# espPixel.net
KiCad netlist of a schematic drawn in EAGLE
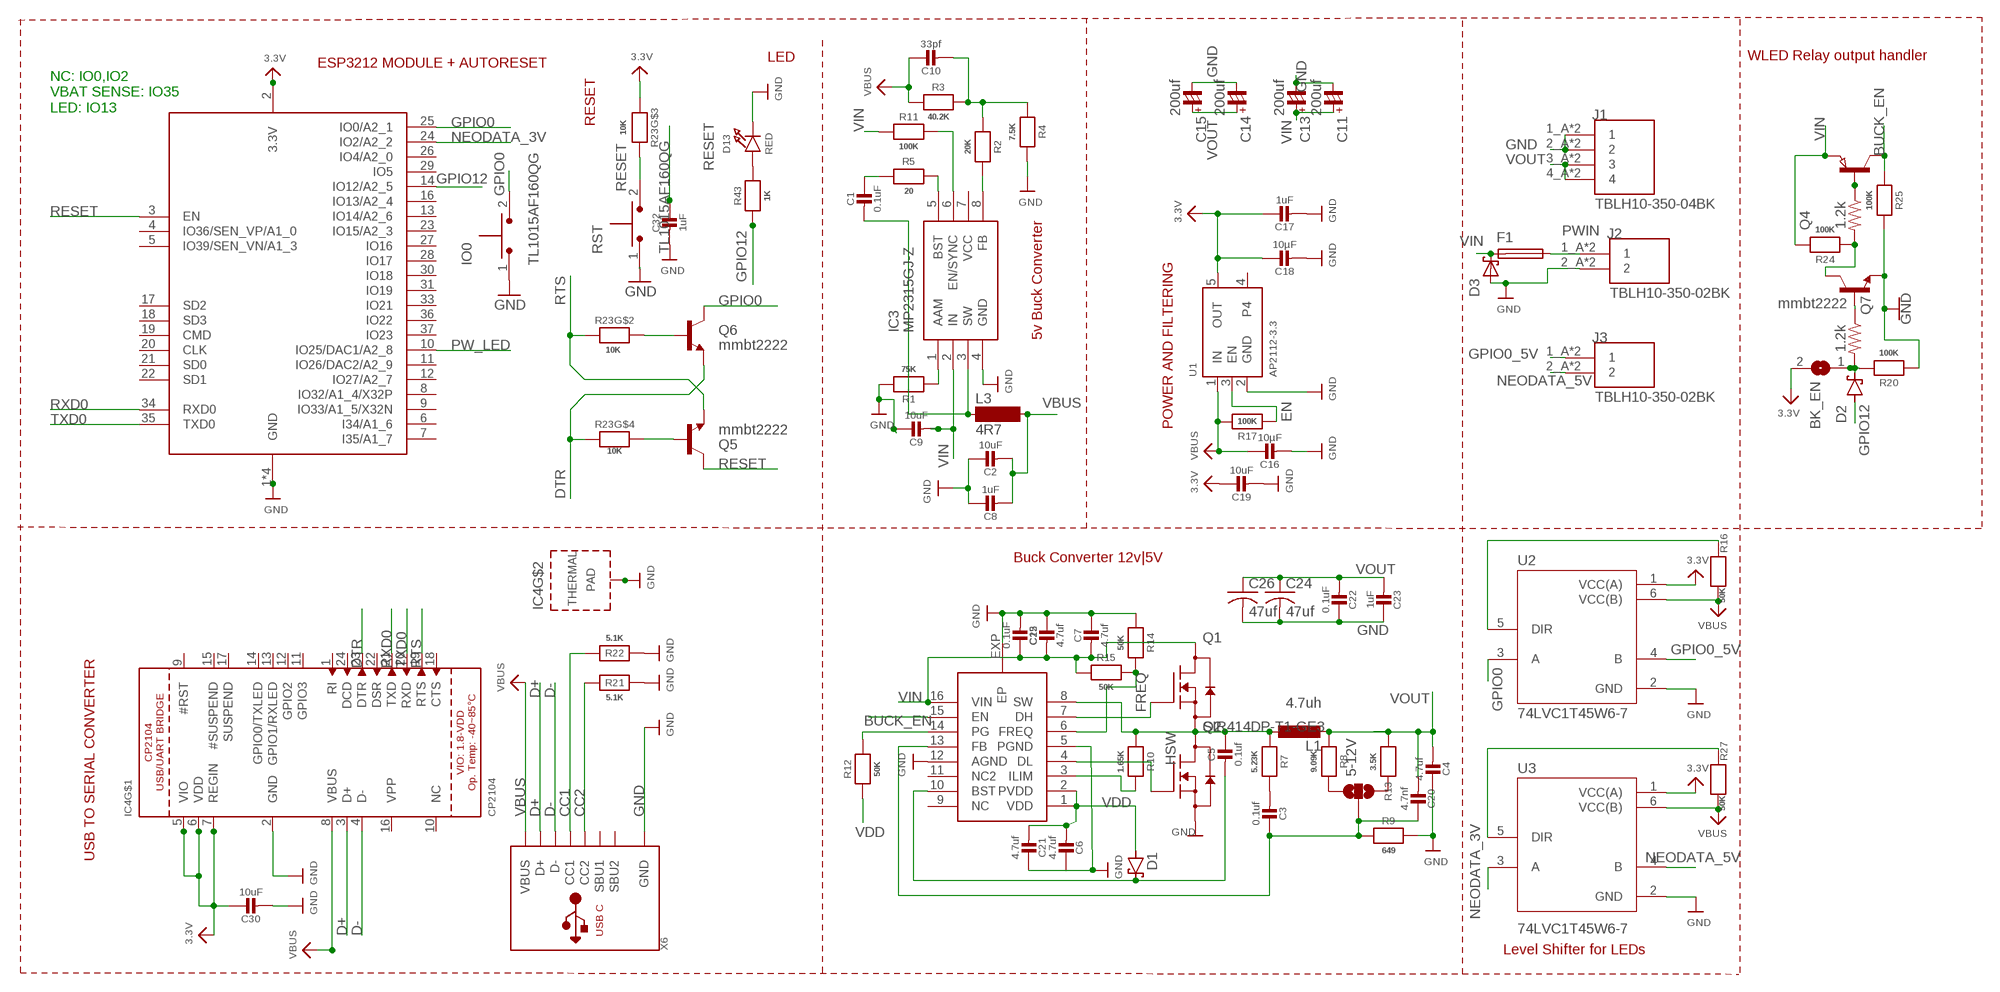
[diagram p0: schematic, sheet 1]

(export (version "E")
  (design (tool "Eeschema 10.0.6"))
  (components
    (comp (ref "5-12V")
      (value "JUMPER-SMT_3_NO_NO-SILK")
      (footprint "eagle-import:SMT-JUMPER_3_NO_NO-SILK")
      (libsource (lib "eagle-import") (part "JUMPER-SMT_3_NO_NO-SILK"))
    )
    (comp (ref "BK_EN")
      (value "SJ")
      (footprint "eagle-import:SJ")
      (libsource (lib "eagle-import") (part "SJ"))
    )
    (comp (ref "C1")
      (value "0.1uF")
      (footprint "eagle-import:0603-NO@1")
      (libsource (lib "eagle-import") (part "CAP_CERAMIC0603_NO"))
    )
    (comp (ref "C2")
      (value "10uF")
      (footprint "eagle-import:0603-NO@1")
      (libsource (lib "eagle-import") (part "CAP_CERAMIC0603_NO"))
    )
    (comp (ref "C3")
      (value "0.1uf")
      (footprint "eagle-import:0603-NO@1")
      (libsource (lib "eagle-import") (part "CAP_CERAMIC0603_NO"))
    )
    (comp (ref "C4")
      (value "4.7uf")
      (footprint "eagle-import:0805_10MGAP")
      (libsource (lib "eagle-import") (part "CAP_CERAMIC0805_10MGAP"))
    )
    (comp (ref "C5")
      (value "0.1uf")
      (footprint "eagle-import:0603-NO@1")
      (libsource (lib "eagle-import") (part "CAP_CERAMIC0603_NO"))
    )
    (comp (ref "C6")
      (value "4.7uf")
      (footprint "eagle-import:0603-NO@1")
      (libsource (lib "eagle-import") (part "CAP_CERAMIC0603_NO"))
    )
    (comp (ref "C7")
      (value "4.7uf")
      (footprint "eagle-import:0805_10MGAP")
      (libsource (lib "eagle-import") (part "CAP_CERAMIC0805_10MGAP"))
    )
    (comp (ref "C8")
      (value "1uF")
      (footprint "eagle-import:0603-NO@1")
      (libsource (lib "eagle-import") (part "CAP_CERAMIC0603_NO"))
    )
    (comp (ref "C9")
      (value "10uF")
      (footprint "eagle-import:0805_10MGAP")
      (libsource (lib "eagle-import") (part "CAP_CERAMIC0805_10MGAP"))
    )
    (comp (ref "C10")
      (value "33pf")
      (footprint "eagle-import:0603-NO@1")
      (libsource (lib "eagle-import") (part "CAP_CERAMIC0603_NO"))
    )
    (comp (ref "C11")
      (value "200uf")
      (footprint "eagle-import:CSV-E_F")
      (libsource (lib "eagle-import") (part "CP_SV-E/F"))
    )
    (comp (ref "C12")
      (value "4.7uf")
      (footprint "eagle-import:0805_10MGAP")
      (libsource (lib "eagle-import") (part "CAP_CERAMIC0805_10MGAP"))
    )
    (comp (ref "C13")
      (value "200uf")
      (footprint "eagle-import:CSV-E_F")
      (libsource (lib "eagle-import") (part "CP_SV-E/F"))
    )
    (comp (ref "C14")
      (value "200uf")
      (footprint "eagle-import:CSV-E_F")
      (libsource (lib "eagle-import") (part "CP_SV-E/F"))
    )
    (comp (ref "C15")
      (value "200uf")
      (footprint "eagle-import:CSV-E_F")
      (libsource (lib "eagle-import") (part "CP_SV-E/F"))
    )
    (comp (ref "C16")
      (value "10µF")
      (footprint "eagle-import:0805-NO")
      (libsource (lib "eagle-import") (part "CAP_CERAMIC0805-NOOUTLINE"))
    )
    (comp (ref "C17")
      (value "1uF")
      (footprint "eagle-import:0603-NO@1")
      (libsource (lib "eagle-import") (part "CAP_CERAMIC0603_NO"))
    )
    (comp (ref "C18")
      (value "10µF")
      (footprint "eagle-import:0805-NO")
      (libsource (lib "eagle-import") (part "CAP_CERAMIC0805-NOOUTLINE"))
    )
    (comp (ref "C19")
      (value "10uF")
      (footprint "eagle-import:0805-NO")
      (libsource (lib "eagle-import") (part "CAP_CERAMIC0805-NOOUTLINE"))
    )
    (comp (ref "C20")
      (value "4.7nf")
      (footprint "eagle-import:0603-NO@1")
      (libsource (lib "eagle-import") (part "CAP_CERAMIC0603_NO"))
    )
    (comp (ref "C21")
      (value "4.7uf")
      (footprint "eagle-import:0603-NO@1")
      (libsource (lib "eagle-import") (part "CAP_CERAMIC0603_NO"))
    )
    (comp (ref "C22")
      (value "0.1uF")
      (footprint "eagle-import:0603-NO@1")
      (libsource (lib "eagle-import") (part "CAP_CERAMIC0603_NO"))
    )
    (comp (ref "C23")
      (value "1uF")
      (footprint "eagle-import:0603-NO@1")
      (libsource (lib "eagle-import") (part "CAP_CERAMIC0603_NO"))
    )
    (comp (ref "C24")
      (value "47uf")
      (footprint "eagle-import:C3225")
      (libsource (lib "eagle-import") (part "C-USC3225"))
    )
    (comp (ref "C25")
      (value "0.1uF")
      (footprint "eagle-import:0603-NO@1")
      (libsource (lib "eagle-import") (part "CAP_CERAMIC0603_NO"))
    )
    (comp (ref "C26")
      (value "47uf")
      (footprint "eagle-import:C3225")
      (libsource (lib "eagle-import") (part "C-USC3225"))
    )
    (comp (ref "C30")
      (value "10uF")
      (footprint "eagle-import:0805-NO")
      (libsource (lib "eagle-import") (part "CAP_CERAMIC0805-NOOUTLINE"))
    )
    (comp (ref "C32")
      (value "1uF")
      (footprint "eagle-import:0603-NO@1")
      (libsource (lib "eagle-import") (part "CAP_CERAMIC0603_NO"))
    )
    (comp (ref "D1")
      (value "BAT60J")
      (footprint "eagle-import:SOD323_ST")
      (libsource (lib "eagle-import") (part "BAT60J"))
    )
    (comp (ref "D2")
      (value "BAT60J")
      (footprint "eagle-import:SOD323_ST")
      (libsource (lib "eagle-import") (part "BAT60J"))
    )
    (comp (ref "D3")
      (value "SCHOTTKY-DIODESMC")
      (footprint "eagle-import:SMC")
      (libsource (lib "eagle-import") (part "SCHOTTKY-DIODESMC"))
    )
    (comp (ref "D13")
      (value "RED")
      (footprint "eagle-import:CHIPLED_0805_NOOUTLINE")
      (libsource (lib "eagle-import") (part "LED0805_NOOUTLINE"))
    )
    (comp (ref "F1")
      (value "SMD-MICRO-FUSE-BLOCK")
      (footprint "eagle-import:OMNIBLOK")
      (libsource (lib "eagle-import") (part "SMD-MICRO-FUSE-BLOCK"))
    )
    (comp (ref "IC3")
      (value "MP2315GJ-Z")
      (footprint "eagle-import:SOT65P280X100-8N")
      (fields (field (name "MOUSER_PART_NUMBER") "946-MP2315GJZ"))
      (libsource (lib "eagle-import") (part "MP2315GJ-Z"))
    )
    (comp (ref "IC4")
      (value "CP2104")
      (footprint "eagle-import:QFN24_4MM_SMSC")
      (libsource (lib "eagle-import") (part "CP2104"))
    )
    (comp (ref "IO0")
      (value "TL1015AF160QG")
      (footprint "eagle-import:SW_TL1015AF160QG")
      (fields (field (name "MF") "E-Switch"))
      (libsource (lib "eagle-import") (part "TL1015AF160QG"))
    )
    (comp (ref "J1")
      (value "TBLH10-350-04BK")
      (footprint "eagle-import:CUI_TBLH10-350-04BK")
      (fields (field (name "MF") "CUI Devices"))
      (libsource (lib "eagle-import") (part "TBLH10-350-04BK"))
    )
    (comp (ref "J2")
      (value "TBLH10-350-02BK")
      (footprint "eagle-import:CUI_TBLH10-350-02BK")
      (fields (field (name "MF") "CUI Devices"))
      (libsource (lib "eagle-import") (part "TBLH10-350-02BK"))
    )
    (comp (ref "J3")
      (value "TBLH10-350-02BK")
      (footprint "eagle-import:CUI_TBLH10-350-02BK")
      (fields (field (name "MF") "CUI Devices"))
      (libsource (lib "eagle-import") (part "TBLH10-350-02BK"))
    )
    (comp (ref "L1")
      (value "4.7uh")
      (footprint "eagle-import:CEP125")
      (libsource (lib "eagle-import") (part "L-EUCEP125"))
    )
    (comp (ref "L3")
      (value "4R7")
      (footprint "eagle-import:MS50")
      (libsource (lib "eagle-import") (part "MS50"))
    )
    (comp (ref "Q1")
      (value "SIR414DP-T1-GE3")
      (footprint "eagle-import:TRANS_SQJ461EP-T1-GE3")
      (fields (field (name "MF") "Vishay Siliconix"))
      (libsource (lib "eagle-import") (part "SIR414DP-T1-GE3"))
    )
    (comp (ref "Q2")
      (value "SIR414DP-T1-GE3")
      (footprint "eagle-import:TRANS_SQJ461EP-T1-GE3")
      (fields (field (name "MF") "Vishay Siliconix"))
      (libsource (lib "eagle-import") (part "SIR414DP-T1-GE3"))
    )
    (comp (ref "Q4")
      (value "PNP-TRANSISTOR_SOT23")
      (footprint "eagle-import:SOT23")
      (libsource (lib "eagle-import") (part "PNP-TRANSISTOR_SOT23"))
    )
    (comp (ref "Q5")
      (value "mmbt2222")
      (footprint "eagle-import:SOT23-3")
      (libsource (lib "eagle-import") (part "TRANSISTOR_NPNSOT23-3"))
    )
    (comp (ref "Q6")
      (value "mmbt2222")
      (footprint "eagle-import:SOT23-3")
      (libsource (lib "eagle-import") (part "TRANSISTOR_NPNSOT23-3"))
    )
    (comp (ref "Q7")
      (value "mmbt2222")
      (footprint "eagle-import:SOT23-3")
      (libsource (lib "eagle-import") (part "TRANSISTOR_NPNSOT23-3"))
    )
    (comp (ref "R1")
      (value "75K")
      (footprint "eagle-import:0603-NO")
      (libsource (lib "eagle-import") (part "RESISTOR_0603_NOOUT"))
    )
    (comp (ref "R2")
      (value "20K")
      (footprint "eagle-import:0603-NO")
      (libsource (lib "eagle-import") (part "RESISTOR_0603_NOOUT"))
    )
    (comp (ref "R3")
      (value "40.2K")
      (footprint "eagle-import:0603-NO")
      (libsource (lib "eagle-import") (part "RESISTOR_0603_NOOUT"))
    )
    (comp (ref "R4")
      (value "7.5K")
      (footprint "eagle-import:0603-NO")
      (libsource (lib "eagle-import") (part "RESISTOR_0603_NOOUT"))
    )
    (comp (ref "R5")
      (value "20")
      (footprint "eagle-import:0603-NO")
      (libsource (lib "eagle-import") (part "RESISTOR_0603_NOOUT"))
    )
    (comp (ref "R6")
      (value "1.2k")
      (footprint "eagle-import:0603")
      (libsource (lib "eagle-import") (part "RESISTOR0603"))
    )
    (comp (ref "R7")
      (value "5.23K")
      (footprint "eagle-import:0603-NO")
      (libsource (lib "eagle-import") (part "RESISTOR_0603_NOOUT"))
    )
    (comp (ref "R8")
      (value "9.09K")
      (footprint "eagle-import:0603-NO")
      (libsource (lib "eagle-import") (part "RESISTOR_0603_NOOUT"))
    )
    (comp (ref "R9")
      (value "649")
      (footprint "eagle-import:0603-NO")
      (libsource (lib "eagle-import") (part "RESISTOR_0603_NOOUT"))
    )
    (comp (ref "R10")
      (value "1.65K")
      (footprint "eagle-import:0603-NO")
      (libsource (lib "eagle-import") (part "RESISTOR_0603_NOOUT"))
    )
    (comp (ref "R11")
      (value "100K")
      (footprint "eagle-import:0603-NO")
      (libsource (lib "eagle-import") (part "RESISTOR_0603_NOOUT"))
    )
    (comp (ref "R12")
      (value "50K")
      (footprint "eagle-import:0603-NO")
      (libsource (lib "eagle-import") (part "RESISTOR_0603_NOOUT"))
    )
    (comp (ref "R13")
      (value "3.5K")
      (footprint "eagle-import:0603-NO")
      (libsource (lib "eagle-import") (part "RESISTOR_0603_NOOUT"))
    )
    (comp (ref "R14")
      (value "50K")
      (footprint "eagle-import:0603-NO")
      (libsource (lib "eagle-import") (part "RESISTOR_0603_NOOUT"))
    )
    (comp (ref "R15")
      (value "50K")
      (footprint "eagle-import:0603-NO")
      (libsource (lib "eagle-import") (part "RESISTOR_0603_NOOUT"))
    )
    (comp (ref "R16")
      (value "50K")
      (footprint "eagle-import:0603-NO")
      (libsource (lib "eagle-import") (part "RESISTOR_0603_NOOUT"))
    )
    (comp (ref "R17")
      (value "100K")
      (footprint "eagle-import:0603-NO")
      (libsource (lib "eagle-import") (part "RESISTOR_0603_NOOUT"))
    )
    (comp (ref "R19")
      (value "1.2k")
      (footprint "eagle-import:0603")
      (libsource (lib "eagle-import") (part "RESISTOR0603"))
    )
    (comp (ref "R20")
      (value "100K")
      (footprint "eagle-import:0603-NO")
      (libsource (lib "eagle-import") (part "RESISTOR_0603_NOOUT"))
    )
    (comp (ref "R21")
      (value "5.1K")
      (footprint "eagle-import:0603-NO")
      (libsource (lib "eagle-import") (part "RESISTOR_0603_NOOUT"))
    )
    (comp (ref "R22")
      (value "5.1K")
      (footprint "eagle-import:0603-NO")
      (libsource (lib "eagle-import") (part "RESISTOR_0603_NOOUT"))
    )
    (comp (ref "R23")
      (value "10K")
      (footprint "eagle-import:RESPACK_4X0603")
      (libsource (lib "eagle-import") (part "RESISTOR_4PACK"))
    )
    (comp (ref "R24")
      (value "100K")
      (footprint "eagle-import:0603-NO")
      (libsource (lib "eagle-import") (part "RESISTOR_0603_NOOUT"))
    )
    (comp (ref "R25")
      (value "100K")
      (footprint "eagle-import:0603-NO")
      (libsource (lib "eagle-import") (part "RESISTOR_0603_NOOUT"))
    )
    (comp (ref "R27")
      (value "50K")
      (footprint "eagle-import:0603-NO")
      (libsource (lib "eagle-import") (part "RESISTOR_0603_NOOUT"))
    )
    (comp (ref "R43")
      (value "1K")
      (footprint "eagle-import:0603-NO")
      (libsource (lib "eagle-import") (part "RESISTOR_0603_NOOUT"))
    )
    (comp (ref "RST")
      (value "TL1015AF160QG")
      (footprint "eagle-import:SW_TL1015AF160QG")
      (fields (field (name "MF") "E-Switch"))
      (libsource (lib "eagle-import") (part "TL1015AF160QG"))
    )
    (comp (ref "U$1")
      (value "MIC2101QFN16")
      (footprint "eagle-import:QFN16")
      (libsource (lib "eagle-import") (part "MIC2101QFN16"))
    )
    (comp (ref "U1")
      (value "AP2112-3.3")
      (footprint "eagle-import:SOT23-5")
      (libsource (lib "eagle-import") (part "VREG_SOT23-5"))
    )
    (comp (ref "U2")
      (value "74LVC1T45W6-7")
      (footprint "eagle-import:SOT95P285X140-6N")
      (fields (field (name "MF") "Diodes Inc."))
      (libsource (lib "eagle-import") (part "74LVC1T45W6-7"))
    )
    (comp (ref "U3")
      (value "74LVC1T45W6-7")
      (footprint "eagle-import:SOT95P285X140-6N")
      (fields (field (name "MF") "Diodes Inc."))
      (libsource (lib "eagle-import") (part "74LVC1T45W6-7"))
    )
    (comp (ref "X6")
      (value "USB_C")
      (footprint "eagle-import:USB_C_CUSB31-CFM2AX-01-X")
      (libsource (lib "eagle-import") (part "USB_C"))
    )
    (comp (ref "X8")
      (value "ESP32_WROOM32_SKINNY")
      (footprint "eagle-import:WROOM32_SKINNY")
      (libsource (lib "eagle-import") (part "ESP32_WROOM32_SKINNY"))
    )
  )
  (nets
    (net (code "1") (name "/BUCK_EN") (class "Default")
      (node (ref "Q4") (pin "3") (pinfunction "C_3") (pintype "passive"))
      (node (ref "R25") (pin "1") (pinfunction "1_1") (pintype "passive"))
      (node (ref "U$1") (pin "15") (pinfunction "EN_15") (pintype "bidirectional"))
    )
    (net (code "2") (name "/CC1") (class "Default")
      (node (ref "R22") (pin "2") (pinfunction "2_2") (pintype "passive"))
      (node (ref "X6") (pin "A5") (pinfunction "CC1_A5") (pintype "bidirectional"))
    )
    (net (code "3") (name "/CC2") (class "Default")
      (node (ref "R21") (pin "2") (pinfunction "2_2") (pintype "passive"))
      (node (ref "X6") (pin "B5") (pinfunction "CC2_B5") (pintype "bidirectional"))
    )
    (net (code "4") (name "/D+") (class "Default")
      (node (ref "IC4") (pin "3") (pinfunction "D+_3") (pintype "bidirectional"))
      (node (ref "X6") (pin "A6") (pinfunction "D+_A6") (pintype "bidirectional"))
      (node (ref "X6") (pin "B6") (pinfunction "D+_B6") (pintype "bidirectional"))
    )
    (net (code "5") (name "/D-") (class "Default")
      (node (ref "IC4") (pin "4") (pinfunction "D-_4") (pintype "bidirectional"))
      (node (ref "X6") (pin "A7") (pinfunction "D-_A7") (pintype "bidirectional"))
      (node (ref "X6") (pin "B7") (pinfunction "D-_B7") (pintype "bidirectional"))
    )
    (net (code "6") (name "/DTR") (class "Default")
      (node (ref "IC4") (pin "23") (pinfunction "DTR_23") (pintype "output"))
      (node (ref "Q6") (pin "2") (pinfunction "E_2") (pintype "passive"))
      (node (ref "R23") (pin "4") (pinfunction "1_4") (pintype "passive"))
    )
    (net (code "7") (name "/EN") (class "Default")
      (node (ref "R17") (pin "1") (pinfunction "1_1") (pintype "passive"))
      (node (ref "U1") (pin "3") (pinfunction "EN_3") (pintype "input"))
    )
    (net (code "8") (name "/FREQ") (class "Default")
      (node (ref "R14") (pin "2") (pinfunction "2_2") (pintype "passive"))
      (node (ref "R15") (pin "2") (pinfunction "2_2") (pintype "passive"))
      (node (ref "U$1") (pin "6") (pinfunction "FREQ_6") (pintype "bidirectional"))
    )
    (net (code "9") (name "/GPIO0") (class "Default")
      (node (ref "IO0") (pin "2") (pinfunction "2_2") (pintype "passive"))
      (node (ref "Q6") (pin "3") (pinfunction "C_3") (pintype "passive"))
      (node (ref "U2") (pin "3") (pinfunction "A_3") (pintype "bidirectional"))
      (node (ref "X8") (pin "25") (pinfunction "IO0/A2_1_25") (pintype "bidirectional"))
    )
    (net (code "10") (name "/GPIO0_5V") (class "Default")
      (node (ref "J3") (pin "1_A") (pinfunction "1_1_A") (pintype "passive"))
      (node (ref "J3") (pin "1_B") (pinfunction "1_1_B") (pintype "passive"))
      (node (ref "U2") (pin "4") (pinfunction "B_4") (pintype "bidirectional"))
    )
    (net (code "11") (name "/GPIO12") (class "Default")
      (node (ref "D2") (pin "A") (pinfunction "A_A") (pintype "passive"))
      (node (ref "R43") (pin "1") (pinfunction "1_1") (pintype "passive"))
      (node (ref "X8") (pin "14") (pinfunction "IO12/A2_5_14") (pintype "bidirectional"))
    )
    (net (code "12") (name "/HSW") (class "Default")
      (node (ref "C5") (pin "1") (pinfunction "1_1") (pintype "passive"))
      (node (ref "L1") (pin "1") (pinfunction "1_1") (pintype "passive"))
      (node (ref "Q1") (pin "1") (pinfunction "S_1") (pintype "passive"))
      (node (ref "Q1") (pin "2") (pinfunction "S_2") (pintype "passive"))
      (node (ref "Q1") (pin "3") (pinfunction "S_3") (pintype "passive"))
      (node (ref "Q2") (pin "5") (pinfunction "D_5") (pintype "passive"))
      (node (ref "Q2") (pin "6") (pinfunction "D_6") (pintype "passive"))
      (node (ref "Q2") (pin "7") (pinfunction "D_7") (pintype "passive"))
      (node (ref "Q2") (pin "8") (pinfunction "D_8") (pintype "passive"))
      (node (ref "Q2") (pin "9") (pinfunction "D_9") (pintype "passive"))
      (node (ref "R10") (pin "1") (pinfunction "1_1") (pintype "passive"))
      (node (ref "R7") (pin "1") (pinfunction "1_1") (pintype "passive"))
      (node (ref "U$1") (pin "8") (pinfunction "SW_8") (pintype "bidirectional"))
    )
    (net (code "13") (name "/NEODATA_3V") (class "Default")
      (node (ref "U3") (pin "3") (pinfunction "A_3") (pintype "bidirectional"))
      (node (ref "X8") (pin "24") (pinfunction "IO2/A2_2_24") (pintype "bidirectional"))
    )
    (net (code "14") (name "/NEODATA_5V") (class "Default")
      (node (ref "J3") (pin "2_A") (pinfunction "2_2_A") (pintype "passive"))
      (node (ref "J3") (pin "2_B") (pinfunction "2_2_B") (pintype "passive"))
      (node (ref "U3") (pin "4") (pinfunction "B_4") (pintype "bidirectional"))
    )
    (net (code "15") (name "/PWIN") (class "Default")
      (node (ref "F1") (pin "P$1") (pinfunction "1_P$1") (pintype "passive"))
      (node (ref "J2") (pin "1_A") (pinfunction "1_1_A") (pintype "passive"))
      (node (ref "J2") (pin "1_B") (pinfunction "1_1_B") (pintype "passive"))
    )
    (net (code "16") (name "/PW_LED") (class "Default")
      (node (ref "X8") (pin "10") (pinfunction "IO25/DAC1/A2_8_10") (pintype "bidirectional"))
    )
    (net (code "17") (name "/RESET") (class "Default")
      (node (ref "C32") (pin "1") (pinfunction "1_1") (pintype "passive"))
      (node (ref "Q5") (pin "3") (pinfunction "C_3") (pintype "passive"))
      (node (ref "R23") (pin "6") (pinfunction "2_6") (pintype "passive"))
      (node (ref "RST") (pin "2") (pinfunction "2_2") (pintype "passive"))
      (node (ref "X8") (pin "3") (pinfunction "EN_3") (pintype "input"))
    )
    (net (code "18") (name "/RTS") (class "Default")
      (node (ref "IC4") (pin "19") (pinfunction "RTS_19") (pintype "output"))
      (node (ref "Q5") (pin "2") (pinfunction "E_2") (pintype "passive"))
      (node (ref "R23") (pin "2") (pinfunction "1_2") (pintype "passive"))
    )
    (net (code "19") (name "/RXD0") (class "Default")
      (node (ref "IC4") (pin "21") (pinfunction "TXD_21") (pintype "output"))
      (node (ref "X8") (pin "34") (pinfunction "RXD0_34") (pintype "input"))
    )
    (net (code "20") (name "/TXD0") (class "Default")
      (node (ref "IC4") (pin "20") (pinfunction "RXD_20") (pintype "input"))
      (node (ref "X8") (pin "35") (pinfunction "TXD0_35") (pintype "output"))
    )
    (net (code "21") (name "/VDD") (class "Default")
      (node (ref "C21") (pin "2") (pinfunction "2_2") (pintype "passive"))
      (node (ref "C6") (pin "2") (pinfunction "2_2") (pintype "passive"))
      (node (ref "D1") (pin "A") (pinfunction "A_A") (pintype "passive"))
      (node (ref "R12") (pin "1") (pinfunction "1_1") (pintype "passive"))
      (node (ref "U$1") (pin "1") (pinfunction "VDD_1") (pintype "power_in"))
      (node (ref "U$1") (pin "2") (pinfunction "PVDD_2") (pintype "bidirectional"))
    )
    (net (code "22") (name "/VIN") (class "Default")
      (node (ref "C11") (pin "+") (pinfunction "+_+") (pintype "passive"))
      (node (ref "C12") (pin "2") (pinfunction "2_2") (pintype "passive"))
      (node (ref "C13") (pin "+") (pinfunction "+_+") (pintype "passive"))
      (node (ref "C25") (pin "1") (pinfunction "1_1") (pintype "passive"))
      (node (ref "C7") (pin "2") (pinfunction "2_2") (pintype "passive"))
      (node (ref "C9") (pin "2") (pinfunction "2_2") (pintype "passive"))
      (node (ref "D3") (pin "C") (pinfunction "C_C") (pintype "passive"))
      (node (ref "F1") (pin "P$2") (pinfunction "2_P$2") (pintype "passive"))
      (node (ref "IC3") (pin "2") (pinfunction "IN_2") (pintype "input"))
      (node (ref "Q1") (pin "5") (pinfunction "D_5") (pintype "passive"))
      (node (ref "Q1") (pin "6") (pinfunction "D_6") (pintype "passive"))
      (node (ref "Q1") (pin "7") (pinfunction "D_7") (pintype "passive"))
      (node (ref "Q1") (pin "8") (pinfunction "D_8") (pintype "passive"))
      (node (ref "Q1") (pin "9") (pinfunction "D_9") (pintype "passive"))
      (node (ref "Q4") (pin "2") (pinfunction "E_2") (pintype "passive"))
      (node (ref "R11") (pin "1") (pinfunction "1_1") (pintype "passive"))
      (node (ref "R15") (pin "1") (pinfunction "1_1") (pintype "passive"))
      (node (ref "R24") (pin "2") (pinfunction "2_2") (pintype "passive"))
      (node (ref "U$1") (pin "16") (pinfunction "VIN_16") (pintype "input"))
    )
    (net (code "23") (name "/VOUT") (class "Default")
      (node (ref "C14") (pin "+") (pinfunction "+_+") (pintype "passive"))
      (node (ref "C15") (pin "+") (pinfunction "+_+") (pintype "passive"))
      (node (ref "C20") (pin "2") (pinfunction "2_2") (pintype "passive"))
      (node (ref "C22") (pin "2") (pinfunction "2_2") (pintype "passive"))
      (node (ref "C23") (pin "2") (pinfunction "2_2") (pintype "passive"))
      (node (ref "C24") (pin "1") (pinfunction "1_1") (pintype "passive"))
      (node (ref "C26") (pin "1") (pinfunction "1_1") (pintype "passive"))
      (node (ref "C4") (pin "2") (pinfunction "2_2") (pintype "passive"))
      (node (ref "J1") (pin "3_A") (pinfunction "3_3_A") (pintype "passive"))
      (node (ref "J1") (pin "3_B") (pinfunction "3_3_B") (pintype "passive"))
      (node (ref "J1") (pin "4_A") (pinfunction "4_4_A") (pintype "passive"))
      (node (ref "J1") (pin "4_B") (pinfunction "4_4_B") (pintype "passive"))
      (node (ref "L1") (pin "2") (pinfunction "2_2") (pintype "passive"))
      (node (ref "R13") (pin "1") (pinfunction "1_1") (pintype "passive"))
      (node (ref "R8") (pin "1") (pinfunction "1_1") (pintype "passive"))
    )
    (net (code "24") (name "3.3V") (class "Default")
      (node (ref "BK_EN") (pin "2") (pinfunction "2_2") (pintype "passive"))
      (node (ref "C17") (pin "1") (pinfunction "1_1") (pintype "passive"))
      (node (ref "C18") (pin "1") (pinfunction "1_1") (pintype "passive"))
      (node (ref "C19") (pin "1") (pinfunction "1_1") (pintype "passive"))
      (node (ref "C30") (pin "1") (pinfunction "1_1") (pintype "passive"))
      (node (ref "IC4") (pin "5") (pinfunction "VIO_5") (pintype "power_in"))
      (node (ref "IC4") (pin "6") (pinfunction "VDD_6") (pintype "power_in"))
      (node (ref "IC4") (pin "7") (pinfunction "REGIN_7") (pintype "power_in"))
      (node (ref "R23") (pin "3") (pinfunction "1_3") (pintype "passive"))
      (node (ref "U1") (pin "5") (pinfunction "OUT_5") (pintype "power_in"))
      (node (ref "U2") (pin "1") (pinfunction "VCC(A)_1") (pintype "power_in"))
      (node (ref "U3") (pin "1") (pinfunction "VCC(A)_1") (pintype "power_in"))
      (node (ref "X8") (pin "2") (pinfunction "3.3V_2") (pintype "passive"))
    )
    (net (code "25") (name "GND") (class "Default")
      (node (ref "C11") (pin "-") (pinfunction "-_-") (pintype "passive"))
      (node (ref "C12") (pin "1") (pinfunction "1_1") (pintype "passive"))
      (node (ref "C13") (pin "-") (pinfunction "-_-") (pintype "passive"))
      (node (ref "C14") (pin "-") (pinfunction "-_-") (pintype "passive"))
      (node (ref "C15") (pin "-") (pinfunction "-_-") (pintype "passive"))
      (node (ref "C16") (pin "2") (pinfunction "2_2") (pintype "passive"))
      (node (ref "C17") (pin "2") (pinfunction "2_2") (pintype "passive"))
      (node (ref "C18") (pin "2") (pinfunction "2_2") (pintype "passive"))
      (node (ref "C19") (pin "2") (pinfunction "2_2") (pintype "passive"))
      (node (ref "C2") (pin "1") (pinfunction "1_1") (pintype "passive"))
      (node (ref "C21") (pin "1") (pinfunction "1_1") (pintype "passive"))
      (node (ref "C22") (pin "1") (pinfunction "1_1") (pintype "passive"))
      (node (ref "C23") (pin "1") (pinfunction "1_1") (pintype "passive"))
      (node (ref "C24") (pin "2") (pinfunction "2_2") (pintype "passive"))
      (node (ref "C25") (pin "2") (pinfunction "2_2") (pintype "passive"))
      (node (ref "C26") (pin "2") (pinfunction "2_2") (pintype "passive"))
      (node (ref "C30") (pin "2") (pinfunction "2_2") (pintype "passive"))
      (node (ref "C32") (pin "2") (pinfunction "2_2") (pintype "passive"))
      (node (ref "C4") (pin "1") (pinfunction "1_1") (pintype "passive"))
      (node (ref "C6") (pin "1") (pinfunction "1_1") (pintype "passive"))
      (node (ref "C7") (pin "1") (pinfunction "1_1") (pintype "passive"))
      (node (ref "C8") (pin "1") (pinfunction "1_1") (pintype "passive"))
      (node (ref "C9") (pin "1") (pinfunction "1_1") (pintype "passive"))
      (node (ref "D13") (pin "C") (pinfunction "C_C") (pintype "passive"))
      (node (ref "D3") (pin "A") (pinfunction "A_A") (pintype "passive"))
      (node (ref "IC3") (pin "4") (pinfunction "GND_4") (pintype "power_in"))
      (node (ref "IC4") (pin "2") (pinfunction "GND_2") (pintype "power_in"))
      (node (ref "IC4") (pin "THERM") (pinfunction "TP_THERM") (pintype "power_in"))
      (node (ref "IO0") (pin "1") (pinfunction "1_1") (pintype "passive"))
      (node (ref "J1") (pin "1_A") (pinfunction "1_1_A") (pintype "passive"))
      (node (ref "J1") (pin "1_B") (pinfunction "1_1_B") (pintype "passive"))
      (node (ref "J1") (pin "2_A") (pinfunction "2_2_A") (pintype "passive"))
      (node (ref "J1") (pin "2_B") (pinfunction "2_2_B") (pintype "passive"))
      (node (ref "J2") (pin "2_A") (pinfunction "2_2_A") (pintype "passive"))
      (node (ref "J2") (pin "2_B") (pinfunction "2_2_B") (pintype "passive"))
      (node (ref "Q2") (pin "1") (pinfunction "S_1") (pintype "passive"))
      (node (ref "Q2") (pin "2") (pinfunction "S_2") (pintype "passive"))
      (node (ref "Q2") (pin "3") (pinfunction "S_3") (pintype "passive"))
      (node (ref "Q7") (pin "2") (pinfunction "E_2") (pintype "passive"))
      (node (ref "R1") (pin "2") (pinfunction "2_2") (pintype "passive"))
      (node (ref "R14") (pin "1") (pinfunction "1_1") (pintype "passive"))
      (node (ref "R20") (pin "1") (pinfunction "1_1") (pintype "passive"))
      (node (ref "R21") (pin "1") (pinfunction "1_1") (pintype "passive"))
      (node (ref "R22") (pin "1") (pinfunction "1_1") (pintype "passive"))
      (node (ref "R25") (pin "2") (pinfunction "2_2") (pintype "passive"))
      (node (ref "R4") (pin "2") (pinfunction "2_2") (pintype "passive"))
      (node (ref "R9") (pin "2") (pinfunction "2_2") (pintype "passive"))
      (node (ref "RST") (pin "1") (pinfunction "1_1") (pintype "passive"))
      (node (ref "U$1") (pin "12") (pinfunction "AGND_12") (pintype "bidirectional"))
      (node (ref "U$1") (pin "5") (pinfunction "PGND_5") (pintype "bidirectional"))
      (node (ref "U$1") (pin "EXP") (pinfunction "EP_EXP") (pintype "bidirectional"))
      (node (ref "U1") (pin "2") (pinfunction "GND_2") (pintype "power_in"))
      (node (ref "U2") (pin "2") (pinfunction "GND_2") (pintype "power_in"))
      (node (ref "U3") (pin "2") (pinfunction "GND_2") (pintype "power_in"))
      (node (ref "X6") (pin "A1B12") (pinfunction "GND_A1B12") (pintype "power_in"))
      (node (ref "X6") (pin "B1A12") (pinfunction "GND_B1A12") (pintype "power_in"))
      (node (ref "X8") (pin "1") (pinfunction "GND_1") (pintype "passive"))
      (node (ref "X8") (pin "15") (pinfunction "GND_15") (pintype "passive"))
      (node (ref "X8") (pin "38") (pinfunction "GND_38") (pintype "passive"))
      (node (ref "X8") (pin "P$1") (pinfunction "GND_P$1") (pintype "passive"))
    )
    (net (code "26") (name "Net-(5-12V-Pad1)") (class "Default")
      (node (ref "5-12V") (pin "1") (pinfunction "1_1") (pintype "passive"))
      (node (ref "R8") (pin "2") (pinfunction "2_2") (pintype "passive"))
    )
    (net (code "27") (name "Net-(5-12V-Pad3)") (class "Default")
      (node (ref "5-12V") (pin "3") (pinfunction "3_3") (pintype "passive"))
      (node (ref "R13") (pin "2") (pinfunction "2_2") (pintype "passive"))
    )
    (net (code "28") (name "Net-(BK_EN-Pad1)") (class "Default")
      (node (ref "BK_EN") (pin "1") (pinfunction "1_1") (pintype "passive"))
      (node (ref "D2") (pin "C") (pinfunction "C_C") (pintype "passive"))
      (node (ref "R20") (pin "2") (pinfunction "2_2") (pintype "passive"))
      (node (ref "R6") (pin "2") (pinfunction "2_2") (pintype "passive"))
    )
    (net (code "29") (name "Net-(C1-Pad1)") (class "Default")
      (node (ref "C1") (pin "1") (pinfunction "1_1") (pintype "passive"))
      (node (ref "R5") (pin "1") (pinfunction "1_1") (pintype "passive"))
    )
    (net (code "30") (name "Net-(C3-Pad2)") (class "Default")
      (node (ref "C3") (pin "2") (pinfunction "2_2") (pintype "passive"))
      (node (ref "R7") (pin "2") (pinfunction "2_2") (pintype "passive"))
    )
    (net (code "31") (name "Net-(C10-Pad2)") (class "Default")
      (node (ref "C10") (pin "2") (pinfunction "2_2") (pintype "passive"))
      (node (ref "R2") (pin "1") (pinfunction "1_1") (pintype "passive"))
      (node (ref "R3") (pin "2") (pinfunction "2_2") (pintype "passive"))
      (node (ref "R4") (pin "1") (pinfunction "1_1") (pintype "passive"))
    )
    (net (code "32") (name "Net-(D13-PadA)") (class "Default")
      (node (ref "D13") (pin "A") (pinfunction "A_A") (pintype "passive"))
      (node (ref "R43") (pin "2") (pinfunction "2_2") (pintype "passive"))
    )
    (net (code "33") (name "Net-(IC3-AAM)") (class "Default")
      (node (ref "IC3") (pin "1") (pinfunction "AAM_1") (pintype "bidirectional"))
      (node (ref "R1") (pin "1") (pinfunction "1_1") (pintype "passive"))
    )
    (net (code "34") (name "Net-(IC3-BST)") (class "Default")
      (node (ref "IC3") (pin "5") (pinfunction "BST_5") (pintype "bidirectional"))
      (node (ref "R5") (pin "2") (pinfunction "2_2") (pintype "passive"))
    )
    (net (code "35") (name "Net-(IC3-EN{slash}SYNC)") (class "Default")
      (node (ref "IC3") (pin "6") (pinfunction "EN/SYNC_6") (pintype "bidirectional"))
      (node (ref "R11") (pin "2") (pinfunction "2_2") (pintype "passive"))
    )
    (net (code "36") (name "Net-(IC3-FB)") (class "Default")
      (node (ref "IC3") (pin "8") (pinfunction "FB_8") (pintype "bidirectional"))
      (node (ref "R2") (pin "2") (pinfunction "2_2") (pintype "passive"))
    )
    (net (code "37") (name "Net-(IC3-SW)") (class "Default")
      (node (ref "C1") (pin "2") (pinfunction "2_2") (pintype "passive"))
      (node (ref "IC3") (pin "3") (pinfunction "SW_3") (pintype "bidirectional"))
      (node (ref "L3") (pin "1") (pinfunction "1_1") (pintype "passive"))
    )
    (net (code "38") (name "Net-(Q1-G)") (class "Default")
      (node (ref "Q1") (pin "4") (pinfunction "G_4") (pintype "passive"))
      (node (ref "U$1") (pin "7") (pinfunction "DH_7") (pintype "bidirectional"))
    )
    (net (code "39") (name "Net-(Q2-G)") (class "Default")
      (node (ref "Q2") (pin "4") (pinfunction "G_4") (pintype "passive"))
      (node (ref "U$1") (pin "4") (pinfunction "DL_4") (pintype "bidirectional"))
    )
    (net (code "40") (name "Net-(Q4-B)") (class "Default")
      (node (ref "Q4") (pin "1") (pinfunction "B_1") (pintype "passive"))
      (node (ref "R19") (pin "1") (pinfunction "1_1") (pintype "passive"))
    )
    (net (code "41") (name "Net-(Q5-B)") (class "Default")
      (node (ref "Q5") (pin "1") (pinfunction "B_1") (pintype "passive"))
      (node (ref "R23") (pin "5") (pinfunction "2_5") (pintype "passive"))
    )
    (net (code "42") (name "Net-(Q6-B)") (class "Default")
      (node (ref "Q6") (pin "1") (pinfunction "B_1") (pintype "passive"))
      (node (ref "R23") (pin "7") (pinfunction "2_7") (pintype "passive"))
    )
    (net (code "43") (name "Net-(Q7-B)") (class "Default")
      (node (ref "Q7") (pin "1") (pinfunction "B_1") (pintype "passive"))
      (node (ref "R6") (pin "1") (pinfunction "1_1") (pintype "passive"))
    )
    (net (code "44") (name "Net-(Q7-C)") (class "Default")
      (node (ref "Q7") (pin "3") (pinfunction "C_3") (pintype "passive"))
      (node (ref "R19") (pin "2") (pinfunction "2_2") (pintype "passive"))
      (node (ref "R24") (pin "1") (pinfunction "1_1") (pintype "passive"))
    )
    (net (code "45") (name "Net-(U$1-BST)") (class "Default")
      (node (ref "C5") (pin "2") (pinfunction "2_2") (pintype "passive"))
      (node (ref "D1") (pin "C") (pinfunction "C_C") (pintype "passive"))
      (node (ref "U$1") (pin "10") (pinfunction "BST_10") (pintype "bidirectional"))
    )
    (net (code "46") (name "Net-(U$1-FB)") (class "Default")
      (node (ref "5-12V") (pin "2") (pinfunction "2_2") (pintype "passive"))
      (node (ref "C20") (pin "1") (pinfunction "1_1") (pintype "passive"))
      (node (ref "C3") (pin "1") (pinfunction "1_1") (pintype "passive"))
      (node (ref "R9") (pin "1") (pinfunction "1_1") (pintype "passive"))
      (node (ref "U$1") (pin "13") (pinfunction "FB_13") (pintype "bidirectional"))
    )
    (net (code "47") (name "Net-(U$1-ILIM)") (class "Default")
      (node (ref "R10") (pin "2") (pinfunction "2_2") (pintype "passive"))
      (node (ref "U$1") (pin "3") (pinfunction "ILIM_3") (pintype "bidirectional"))
    )
    (net (code "48") (name "Net-(U$1-PG)") (class "Default")
      (node (ref "R12") (pin "2") (pinfunction "2_2") (pintype "passive"))
      (node (ref "U$1") (pin "14") (pinfunction "PG_14") (pintype "bidirectional"))
    )
    (net (code "49") (name "Net-(U2-DIR)") (class "Default")
      (node (ref "R16") (pin "1") (pinfunction "1_1") (pintype "passive"))
      (node (ref "U2") (pin "5") (pinfunction "DIR_5") (pintype "input"))
    )
    (net (code "50") (name "Net-(U3-DIR)") (class "Default")
      (node (ref "R27") (pin "1") (pinfunction "1_1") (pintype "passive"))
      (node (ref "U3") (pin "5") (pinfunction "DIR_5") (pintype "input"))
    )
    (net (code "51") (name "VBUS") (class "Default")
      (node (ref "C10") (pin "1") (pinfunction "1_1") (pintype "passive"))
      (node (ref "C16") (pin "1") (pinfunction "1_1") (pintype "passive"))
      (node (ref "C2") (pin "2") (pinfunction "2_2") (pintype "passive"))
      (node (ref "C8") (pin "2") (pinfunction "2_2") (pintype "passive"))
      (node (ref "IC4") (pin "8") (pinfunction "VBUS_8") (pintype "power_in"))
      (node (ref "L3") (pin "2") (pinfunction "2_2") (pintype "passive"))
      (node (ref "R16") (pin "2") (pinfunction "2_2") (pintype "passive"))
      (node (ref "R17") (pin "2") (pinfunction "2_2") (pintype "passive"))
      (node (ref "R27") (pin "2") (pinfunction "2_2") (pintype "passive"))
      (node (ref "R3") (pin "1") (pinfunction "1_1") (pintype "passive"))
      (node (ref "U1") (pin "1") (pinfunction "IN_1") (pintype "power_in"))
      (node (ref "U2") (pin "6") (pinfunction "VCC(B)_6") (pintype "power_in"))
      (node (ref "U3") (pin "6") (pinfunction "VCC(B)_6") (pintype "power_in"))
      (node (ref "X6") (pin "A4B9") (pinfunction "VBUS_A4B9") (pintype "power_in"))
      (node (ref "X6") (pin "B4A9") (pinfunction "VBUS_B4A9") (pintype "power_in"))
    )
    (net (code "52") (name "unconnected-(IC3-VCC-Pad7)") (class "Default")
      (node (ref "IC3") (pin "7") (pinfunction "VCC_7") (pintype "bidirectional"))
    )
    (net (code "53") (name "unconnected-(IC4A-#RST-Pad9)") (class "Default")
      (node (ref "IC4") (pin "9") (pinfunction "#RST_9") (pintype "bidirectional"))
    )
    (net (code "54") (name "unconnected-(IC4A-#SUSPEND-Pad15)") (class "Default")
      (node (ref "IC4") (pin "15") (pinfunction "#SUSPEND_15") (pintype "output"))
    )
    (net (code "55") (name "unconnected-(IC4A-CTS-Pad18)") (class "Default")
      (node (ref "IC4") (pin "18") (pinfunction "CTS_18") (pintype "input"))
    )
    (net (code "56") (name "unconnected-(IC4A-DCD-Pad24)") (class "Default")
      (node (ref "IC4") (pin "24") (pinfunction "DCD_24") (pintype "input"))
    )
    (net (code "57") (name "unconnected-(IC4A-DSR-Pad22)") (class "Default")
      (node (ref "IC4") (pin "22") (pinfunction "DSR_22") (pintype "input"))
    )
    (net (code "58") (name "unconnected-(IC4A-GPIO0{slash}TXLED-Pad14)") (class "Default")
      (node (ref "IC4") (pin "14") (pinfunction "GPIO0/TXLED_14") (pintype "bidirectional"))
    )
    (net (code "59") (name "unconnected-(IC4A-GPIO1{slash}RXLED-Pad13)") (class "Default")
      (node (ref "IC4") (pin "13") (pinfunction "GPIO1/RXLED_13") (pintype "bidirectional"))
    )
    (net (code "60") (name "unconnected-(IC4A-GPIO2-Pad12)") (class "Default")
      (node (ref "IC4") (pin "12") (pinfunction "GPIO2_12") (pintype "bidirectional"))
    )
    (net (code "61") (name "unconnected-(IC4A-GPIO3-Pad11)") (class "Default")
      (node (ref "IC4") (pin "11") (pinfunction "GPIO3_11") (pintype "bidirectional"))
    )
    (net (code "62") (name "unconnected-(IC4A-NC-Pad10)") (class "Default")
      (node (ref "IC4") (pin "10") (pinfunction "NC_10") (pintype "no_connect"))
    )
    (net (code "63") (name "unconnected-(IC4A-RI-Pad1)") (class "Default")
      (node (ref "IC4") (pin "1") (pinfunction "RI_1") (pintype "input"))
    )
    (net (code "64") (name "unconnected-(IC4A-SUSPEND-Pad17)") (class "Default")
      (node (ref "IC4") (pin "17") (pinfunction "SUSPEND_17") (pintype "output"))
    )
    (net (code "65") (name "unconnected-(IC4A-VPP-Pad16)") (class "Default")
      (node (ref "IC4") (pin "16") (pinfunction "VPP_16") (pintype "bidirectional"))
    )
    (net (code "66") (name "unconnected-(U$1-NC-Pad9)") (class "Default")
      (node (ref "U$1") (pin "9") (pinfunction "NC_9") (pintype "no_connect"))
    )
    (net (code "67") (name "unconnected-(U$1-NC2-Pad11)") (class "Default")
      (node (ref "U$1") (pin "11") (pinfunction "NC2_11") (pintype "no_connect"))
    )
    (net (code "68") (name "unconnected-(U1-P4-Pad4)") (class "Default")
      (node (ref "U1") (pin "4") (pinfunction "P4_4") (pintype "bidirectional"))
    )
    (net (code "69") (name "unconnected-(X6-SBU1-PadA8)") (class "Default")
      (node (ref "X6") (pin "A8") (pinfunction "SBU1_A8") (pintype "bidirectional"))
    )
    (net (code "70") (name "unconnected-(X6-SBU2-PadB8)") (class "Default")
      (node (ref "X6") (pin "B8") (pinfunction "SBU2_B8") (pintype "bidirectional"))
    )
    (net (code "71") (name "unconnected-(X8-CLK-Pad20)") (class "Default")
      (node (ref "X8") (pin "20") (pinfunction "CLK_20") (pintype "bidirectional"))
    )
    (net (code "72") (name "unconnected-(X8-CMD-Pad19)") (class "Default")
      (node (ref "X8") (pin "19") (pinfunction "CMD_19") (pintype "bidirectional"))
    )
    (net (code "73") (name "unconnected-(X8-I34{slash}A1_6-Pad6)") (class "Default")
      (node (ref "X8") (pin "6") (pinfunction "I34/A1_6_6") (pintype "bidirectional"))
    )
    (net (code "74") (name "unconnected-(X8-I35{slash}A1_7-Pad7)") (class "Default")
      (node (ref "X8") (pin "7") (pinfunction "I35/A1_7_7") (pintype "bidirectional"))
    )
    (net (code "75") (name "unconnected-(X8-IO4{slash}A2_0-Pad26)") (class "Default")
      (node (ref "X8") (pin "26") (pinfunction "IO4/A2_0_26") (pintype "bidirectional"))
    )
    (net (code "76") (name "unconnected-(X8-IO5-Pad29)") (class "Default")
      (node (ref "X8") (pin "29") (pinfunction "IO5_29") (pintype "bidirectional"))
    )
    (net (code "77") (name "unconnected-(X8-IO13{slash}A2_4-Pad16)") (class "Default")
      (node (ref "X8") (pin "16") (pinfunction "IO13/A2_4_16") (pintype "bidirectional"))
    )
    (net (code "78") (name "unconnected-(X8-IO14{slash}A2_6-Pad13)") (class "Default")
      (node (ref "X8") (pin "13") (pinfunction "IO14/A2_6_13") (pintype "bidirectional"))
    )
    (net (code "79") (name "unconnected-(X8-IO15{slash}A2_3-Pad23)") (class "Default")
      (node (ref "X8") (pin "23") (pinfunction "IO15/A2_3_23") (pintype "bidirectional"))
    )
    (net (code "80") (name "unconnected-(X8-IO16-Pad27)") (class "Default")
      (node (ref "X8") (pin "27") (pinfunction "IO16_27") (pintype "bidirectional"))
    )
    (net (code "81") (name "unconnected-(X8-IO17-Pad28)") (class "Default")
      (node (ref "X8") (pin "28") (pinfunction "IO17_28") (pintype "bidirectional"))
    )
    (net (code "82") (name "unconnected-(X8-IO18-Pad30)") (class "Default")
      (node (ref "X8") (pin "30") (pinfunction "IO18_30") (pintype "bidirectional"))
    )
    (net (code "83") (name "unconnected-(X8-IO19-Pad31)") (class "Default")
      (node (ref "X8") (pin "31") (pinfunction "IO19_31") (pintype "bidirectional"))
    )
    (net (code "84") (name "unconnected-(X8-IO21-Pad33)") (class "Default")
      (node (ref "X8") (pin "33") (pinfunction "IO21_33") (pintype "bidirectional"))
    )
    (net (code "85") (name "unconnected-(X8-IO22-Pad36)") (class "Default")
      (node (ref "X8") (pin "36") (pinfunction "IO22_36") (pintype "bidirectional"))
    )
    (net (code "86") (name "unconnected-(X8-IO23-Pad37)") (class "Default")
      (node (ref "X8") (pin "37") (pinfunction "IO23_37") (pintype "bidirectional"))
    )
    (net (code "87") (name "unconnected-(X8-IO26{slash}DAC2{slash}A2_9-Pad11)") (class "Default")
      (node (ref "X8") (pin "11") (pinfunction "IO26/DAC2/A2_9_11") (pintype "bidirectional"))
    )
    (net (code "88") (name "unconnected-(X8-IO27{slash}A2_7-Pad12)") (class "Default")
      (node (ref "X8") (pin "12") (pinfunction "IO27/A2_7_12") (pintype "bidirectional"))
    )
    (net (code "89") (name "unconnected-(X8-IO32{slash}A1_4{slash}X32P-Pad8)") (class "Default")
      (node (ref "X8") (pin "8") (pinfunction "IO32/A1_4/X32P_8") (pintype "bidirectional"))
    )
    (net (code "90") (name "unconnected-(X8-IO33{slash}A1_5{slash}X32N-Pad9)") (class "Default")
      (node (ref "X8") (pin "9") (pinfunction "IO33/A1_5/X32N_9") (pintype "bidirectional"))
    )
    (net (code "91") (name "unconnected-(X8-IO36{slash}SEN_VP{slash}A1_0-Pad4)") (class "Default")
      (node (ref "X8") (pin "4") (pinfunction "IO36/SEN_VP/A1_0_4") (pintype "passive"))
    )
    (net (code "92") (name "unconnected-(X8-IO39{slash}SEN_VN{slash}A1_3-Pad5)") (class "Default")
      (node (ref "X8") (pin "5") (pinfunction "IO39/SEN_VN/A1_3_5") (pintype "passive"))
    )
    (net (code "93") (name "unconnected-(X8-SD0-Pad21)") (class "Default")
      (node (ref "X8") (pin "21") (pinfunction "SD0_21") (pintype "bidirectional"))
    )
    (net (code "94") (name "unconnected-(X8-SD1-Pad22)") (class "Default")
      (node (ref "X8") (pin "22") (pinfunction "SD1_22") (pintype "bidirectional"))
    )
    (net (code "95") (name "unconnected-(X8-SD2-Pad17)") (class "Default")
      (node (ref "X8") (pin "17") (pinfunction "SD2_17") (pintype "bidirectional"))
    )
    (net (code "96") (name "unconnected-(X8-SD3-Pad18)") (class "Default")
      (node (ref "X8") (pin "18") (pinfunction "SD3_18") (pintype "bidirectional"))
    )
  )
)
